# Potencia.net
KiCad netlist of a schematic drawn in Altium Designer
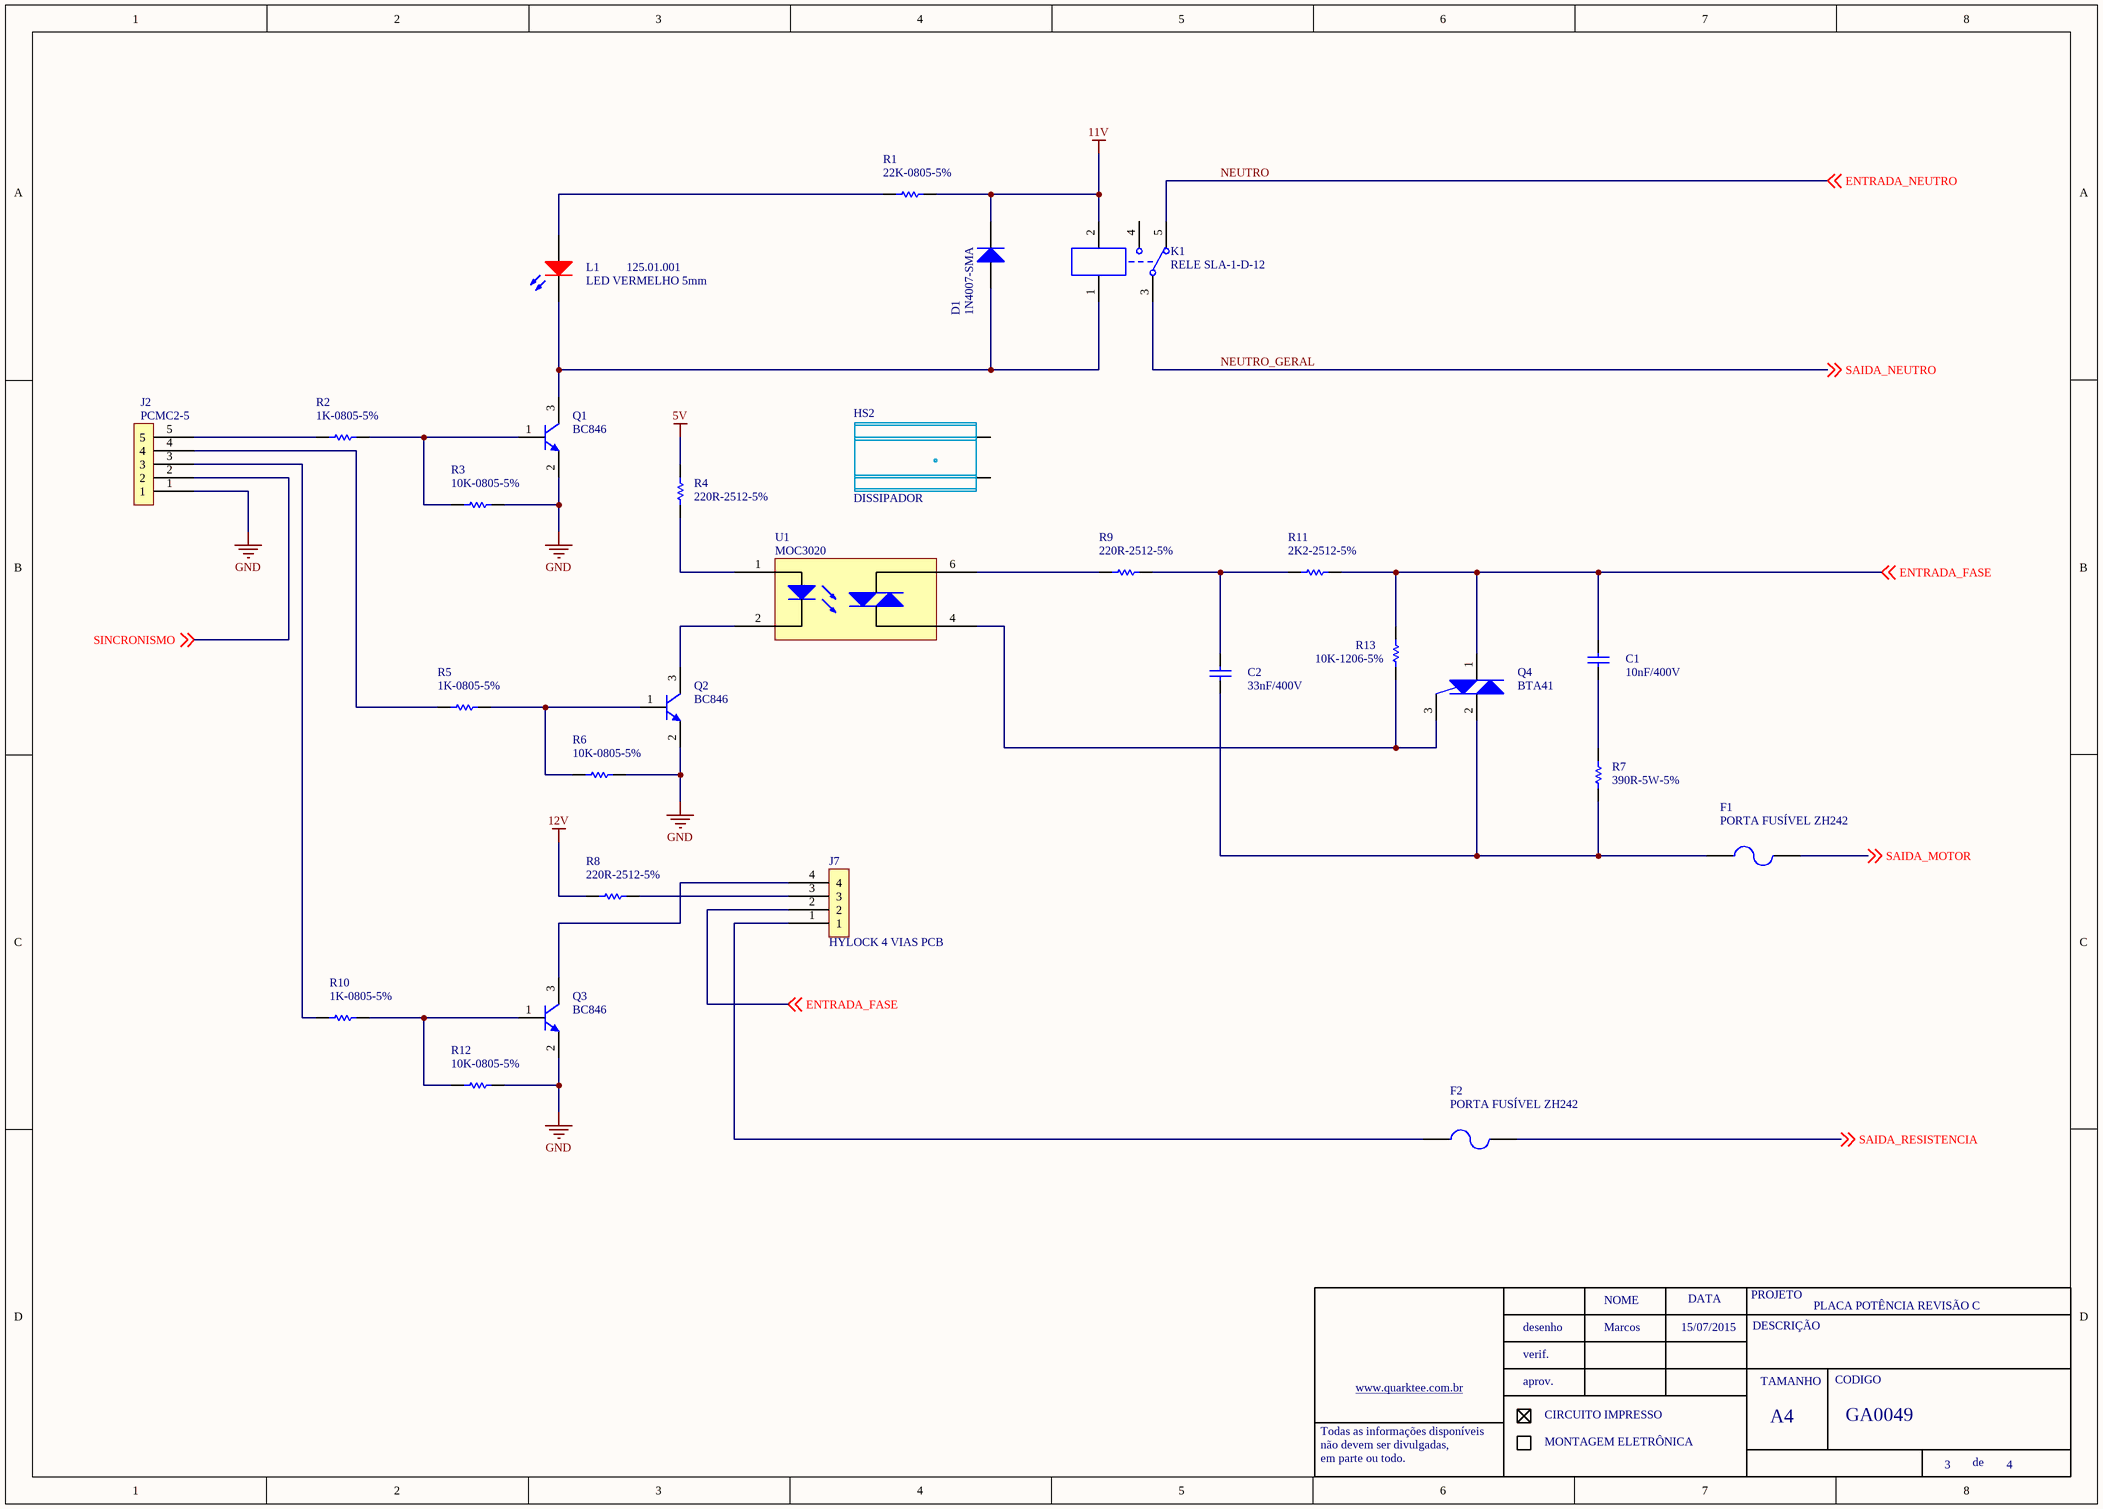
[diagram p0: Potencia.SchDoc]

(export (version "E")
  (design (tool "Eeschema 10.0.6"))
  (components
    (comp (ref "C1")
      (value "10nF/400V")
      (footprint "cap 330nF/250V")
      (description "100nF/50-0805-NPO")
      (libsource (lib "AquinoLib") (part "100nF/50-0805-NPO"))
    )
    (comp (ref "C2")
      (value "33nF/400V")
      (footprint "cap 330nF/250V")
      (description "100nF/50-0805-NPO")
      (libsource (lib "AquinoLib") (part "100nF/50-0805-NPO"))
    )
    (comp (ref "D1")
      (value "1N4007-SMA")
      (footprint "SMA DIODES")
      (description "1N4007")
      (libsource (lib "AquinoLib") (part "1N4007"))
    )
    (comp (ref "F1")
      (value "PORTA FUSÍVEL ZH242")
      (footprint "ZH242_REVISADO")
      (description "PORTA FUSÍVEL TIPO BERÇO")
      (libsource (lib "ChaveDigital3") (part "PORTA FUSÍVEL TIPO BERÇO"))
    )
    (comp (ref "F2")
      (value "PORTA FUSÍVEL ZH242")
      (footprint "ZH242_REVISADO")
      (description "PORTA FUSÍVEL TIPO BERÇO")
      (libsource (lib "ChaveDigital3") (part "PORTA FUSÍVEL TIPO BERÇO"))
    )
    (comp (ref "HS2") (value "DISSIPADOR") (libsource (lib "ChaveDigital3") (part "DISSIPADOR 40mm PÉ")))
    (comp (ref "J2") (value "PCMC2-5") (footprint "PCMC2-5") (libsource (lib "AquinoLib") (part "PCMC2-5")))
    (comp (ref "J7")
      (value "HYLOCK 4 VIAS PCB")
      (footprint "CONECTOR HYLOK 4 VIAS")
      (description "PCMC2-4")
      (libsource (lib "AquinoLib") (part "PCMC2-4"))
    )
    (comp (ref "K1")
      (value "RELE SLA-1-D-12")
      (footprint "rele gigante")
      (description "AT1RC2")
      (libsource (lib "ChaveDigital3") (part "AT1RC2"))
    )
    (comp (ref "L1")
      (value "LED VERMELHO 5mm")
      (footprint "LED 1206")
      (fields (field (name "ERP") "125.01.001"))
      (libsource (lib "AquinoLib") (part "LED VERMELHO 5mm"))
    )
    (comp (ref "Q1")
      (value "BC846")
      (footprint "SOT23 - REVISADO ONDA")
      (description "BC846L")
      (libsource (lib "AquinoLib") (part "BC846"))
    )
    (comp (ref "Q2")
      (value "BC846")
      (footprint "SOT23 - REVISADO ONDA")
      (description "BC846L")
      (libsource (lib "AquinoLib") (part "BC846"))
    )
    (comp (ref "Q3")
      (value "BC846")
      (footprint "SOT23 - REVISADO ONDA")
      (description "BC846L")
      (libsource (lib "AquinoLib") (part "BC846"))
    )
    (comp (ref "Q4")
      (value "BTA41")
      (footprint "TO-247 - duplicate")
      (description "BT134")
      (libsource (lib "AquinoLib") (part "BT134-TO220"))
    )
    (comp (ref "R1")
      (value "22K-0805-5%")
      (footprint "0805-REVISADO ONDA")
      (description "220R-2512-5%")
      (libsource (lib "AquinoLib") (part "220R-2512-5%"))
    )
    (comp (ref "R2")
      (value "1K-0805-5%")
      (footprint "0805-REVISADO ONDA")
      (description "10K-0805-5%")
      (libsource (lib "AquinoLib") (part "10K-0805-5%"))
    )
    (comp (ref "R3")
      (value "10K-0805-5%")
      (footprint "0805-REVISADO ONDA")
      (libsource (lib "AquinoLib") (part "10K-0805-5%"))
    )
    (comp (ref "R4")
      (value "220R-2512-5%")
      (footprint "2512 - REVISADO ONDA")
      (libsource (lib "AquinoLib") (part "220R-2512-5%"))
    )
    (comp (ref "R5")
      (value "1K-0805-5%")
      (footprint "0805-REVISADO ONDA")
      (description "10K-0805-5%")
      (libsource (lib "AquinoLib") (part "10K-0805-5%"))
    )
    (comp (ref "R6")
      (value "10K-0805-5%")
      (footprint "0805-REVISADO ONDA")
      (libsource (lib "AquinoLib") (part "10K-0805-5%"))
    )
    (comp (ref "R7")
      (value "390R-5W-5%")
      (footprint "RESISTOR 5W FIO")
      (description "47R-5W-5%")
      (libsource (lib "AquinoLib") (part "47R-5W-5%"))
    )
    (comp (ref "R8")
      (value "220R-2512-5%")
      (footprint "2512 - REVISADO ONDA")
      (libsource (lib "AquinoLib") (part "220R-2512-5%"))
    )
    (comp (ref "R9")
      (value "220R-2512-5%")
      (footprint "2512 - REVISADO ONDA")
      (libsource (lib "AquinoLib") (part "220R-2512-5%"))
    )
    (comp (ref "R10")
      (value "1K-0805-5%")
      (footprint "0805-REVISADO ONDA")
      (description "10K-0805-5%")
      (libsource (lib "AquinoLib") (part "10K-0805-5%"))
    )
    (comp (ref "R11")
      (value "2K2-2512-5%")
      (footprint "2512 - REVISADO ONDA")
      (description "220R-2512-5%")
      (libsource (lib "AquinoLib") (part "220R-2512-5%"))
    )
    (comp (ref "R12")
      (value "10K-0805-5%")
      (footprint "0805-REVISADO ONDA")
      (libsource (lib "AquinoLib") (part "10K-0805-5%"))
    )
    (comp (ref "R13")
      (value "10K-1206-5%")
      (footprint "1206-REVISADO ONDA")
      (description "220R-2512-5%")
      (libsource (lib "AquinoLib") (part "220R-2512-5%"))
    )
    (comp (ref "U1") (value "MOC3020") (footprint "dip6") (libsource (lib "AquinoLib") (part "MOC3020")))
  )
  (nets
    (net (code "1") (name "5V") (class "Default")
      (node (ref "R4") (pin "1") (pinfunction "1_1") (pintype "passive"))
    )
    (net (code "2") (name "11V") (class "Default")
      (node (ref "D1") (pin "2") (pinfunction "K_2") (pintype "passive"))
      (node (ref "K1") (pin "2") (pinfunction "2_2") (pintype "passive"))
      (node (ref "R1") (pin "1") (pinfunction "1_1") (pintype "passive"))
    )
    (net (code "3") (name "12V") (class "Default")
      (node (ref "R8") (pin "2") (pinfunction "2_2") (pintype "passive"))
    )
    (net (code "4") (name "ENTRADA_FASE") (class "Default")
      (node (ref "C1") (pin "2") (pinfunction "2_2") (pintype "passive"))
      (node (ref "J7") (pin "2") (pinfunction "2_2") (pintype "passive"))
      (node (ref "Q4") (pin "1") (pinfunction "MT1_1") (pintype "passive"))
      (node (ref "R11") (pin "2") (pinfunction "2_2") (pintype "passive"))
      (node (ref "R13") (pin "2") (pinfunction "2_2") (pintype "passive"))
    )
    (net (code "5") (name "ENTRADA_NEUTRO") (class "Default")
      (node (ref "K1") (pin "5") (pinfunction "5_5") (pintype "passive"))
    )
    (net (code "6") (name "GND") (class "Default")
      (node (ref "J2") (pin "1") (pinfunction "1_1") (pintype "passive"))
      (node (ref "Q1") (pin "2") (pinfunction "E_2") (pintype "passive"))
      (node (ref "Q2") (pin "2") (pinfunction "E_2") (pintype "passive"))
      (node (ref "Q3") (pin "2") (pinfunction "E_2") (pintype "passive"))
      (node (ref "R12") (pin "2") (pinfunction "2_2") (pintype "passive"))
      (node (ref "R3") (pin "2") (pinfunction "2_2") (pintype "passive"))
      (node (ref "R6") (pin "2") (pinfunction "2_2") (pintype "passive"))
    )
    (net (code "7") (name "Net-(C1-Pad1)") (class "Default")
      (node (ref "C1") (pin "1") (pinfunction "1_1") (pintype "passive"))
      (node (ref "R7") (pin "1") (pinfunction "1_1") (pintype "passive"))
    )
    (net (code "8") (name "Net-(C2-Pad2)") (class "Default")
      (node (ref "C2") (pin "2") (pinfunction "2_2") (pintype "passive"))
      (node (ref "R11") (pin "1") (pinfunction "1_1") (pintype "passive"))
      (node (ref "R9") (pin "2") (pinfunction "2_2") (pintype "passive"))
    )
    (net (code "9") (name "Net-(D1-A)") (class "Default")
      (node (ref "D1") (pin "1") (pinfunction "A_1") (pintype "passive"))
      (node (ref "K1") (pin "1") (pinfunction "1_1") (pintype "passive"))
      (node (ref "L1") (pin "2") (pinfunction "K_2") (pintype "passive"))
      (node (ref "Q1") (pin "3") (pinfunction "C_3") (pintype "passive"))
    )
    (net (code "10") (name "Net-(F2-Pad2)") (class "Default")
      (node (ref "F2") (pin "2") (pinfunction "2_2") (pintype "passive"))
      (node (ref "J7") (pin "1") (pinfunction "1_1") (pintype "passive"))
    )
    (net (code "11") (name "Net-(J2-Pad3)") (class "Default")
      (node (ref "J2") (pin "3") (pinfunction "3_3") (pintype "passive"))
      (node (ref "R10") (pin "1") (pinfunction "1_1") (pintype "passive"))
    )
    (net (code "12") (name "Net-(J2-Pad4)") (class "Default")
      (node (ref "J2") (pin "4") (pinfunction "4_4") (pintype "passive"))
      (node (ref "R5") (pin "1") (pinfunction "1_1") (pintype "passive"))
    )
    (net (code "13") (name "Net-(J2-Pad5)") (class "Default")
      (node (ref "J2") (pin "5") (pinfunction "5_5") (pintype "passive"))
      (node (ref "R2") (pin "1") (pinfunction "1_1") (pintype "passive"))
    )
    (net (code "14") (name "Net-(J7-Pad3)") (class "Default")
      (node (ref "J7") (pin "3") (pinfunction "3_3") (pintype "passive"))
      (node (ref "R8") (pin "1") (pinfunction "1_1") (pintype "passive"))
    )
    (net (code "15") (name "Net-(L1-A)") (class "Default")
      (node (ref "L1") (pin "1") (pinfunction "A_1") (pintype "passive"))
      (node (ref "R1") (pin "2") (pinfunction "2_2") (pintype "passive"))
    )
    (net (code "16") (name "Net-(Q1-B)") (class "Default")
      (node (ref "Q1") (pin "1") (pinfunction "B_1") (pintype "passive"))
      (node (ref "R2") (pin "2") (pinfunction "2_2") (pintype "passive"))
      (node (ref "R3") (pin "1") (pinfunction "1_1") (pintype "passive"))
    )
    (net (code "17") (name "Net-(Q2-B)") (class "Default")
      (node (ref "Q2") (pin "1") (pinfunction "B_1") (pintype "passive"))
      (node (ref "R5") (pin "2") (pinfunction "2_2") (pintype "passive"))
      (node (ref "R6") (pin "1") (pinfunction "1_1") (pintype "passive"))
    )
    (net (code "18") (name "Net-(Q2-C)") (class "Default")
      (node (ref "Q2") (pin "3") (pinfunction "C_3") (pintype "passive"))
      (node (ref "U1") (pin "2") (pinfunction "2_2") (pintype "passive"))
    )
    (net (code "19") (name "Net-(Q3-B)") (class "Default")
      (node (ref "Q3") (pin "1") (pinfunction "B_1") (pintype "passive"))
      (node (ref "R10") (pin "2") (pinfunction "2_2") (pintype "passive"))
      (node (ref "R12") (pin "1") (pinfunction "1_1") (pintype "passive"))
    )
    (net (code "20") (name "Net-(Q3-C)") (class "Default")
      (node (ref "J7") (pin "4") (pinfunction "4_4") (pintype "passive"))
      (node (ref "Q3") (pin "3") (pinfunction "C_3") (pintype "passive"))
    )
    (net (code "21") (name "Net-(Q4-GATE)") (class "Default")
      (node (ref "Q4") (pin "3") (pinfunction "GATE_3") (pintype "passive"))
      (node (ref "R13") (pin "1") (pinfunction "1_1") (pintype "passive"))
      (node (ref "U1") (pin "4") (pinfunction "4_4") (pintype "passive"))
    )
    (net (code "22") (name "Net-(Q4-MT2)") (class "Default")
      (node (ref "C2") (pin "1") (pinfunction "1_1") (pintype "passive"))
      (node (ref "F1") (pin "2") (pinfunction "2_2") (pintype "passive"))
      (node (ref "Q4") (pin "2") (pinfunction "MT2_2") (pintype "passive"))
      (node (ref "R7") (pin "2") (pinfunction "2_2") (pintype "passive"))
    )
    (net (code "23") (name "Net-(R4-Pad2)") (class "Default")
      (node (ref "R4") (pin "2") (pinfunction "2_2") (pintype "passive"))
      (node (ref "U1") (pin "1") (pinfunction "1_1") (pintype "passive"))
    )
    (net (code "24") (name "Net-(R9-Pad1)") (class "Default")
      (node (ref "R9") (pin "1") (pinfunction "1_1") (pintype "passive"))
      (node (ref "U1") (pin "6") (pinfunction "6_6") (pintype "passive"))
    )
    (net (code "25") (name "SAIDA_MOTOR") (class "Default")
      (node (ref "F1") (pin "1") (pinfunction "1_1") (pintype "passive"))
    )
    (net (code "26") (name "SAIDA_NEUTRO") (class "Default")
      (node (ref "K1") (pin "3") (pinfunction "3_3") (pintype "passive"))
    )
    (net (code "27") (name "SAIDA_RESISTENCIA") (class "Default")
      (node (ref "F2") (pin "1") (pinfunction "1_1") (pintype "passive"))
    )
    (net (code "28") (name "SINCRONISMO") (class "Default")
      (node (ref "J2") (pin "2") (pinfunction "2_2") (pintype "passive"))
    )
    (net (code "29") (name "unconnected-(HS2-Pad0)") (class "Default")
      (node (ref "HS2") (pin "0") (pinfunction "0_0") (pintype "passive"))
    )
    (net (code "30") (name "unconnected-(HS2-Pad1)") (class "Default")
      (node (ref "HS2") (pin "1") (pinfunction "1_1") (pintype "passive"))
    )
    (net (code "31") (name "unconnected-(K1-Pad4)") (class "Default")
      (node (ref "K1") (pin "4") (pinfunction "4_4") (pintype "passive"))
    )
  )
)
